# rzlblink_v2a.net
KiCad netlist of a schematic drawn in EAGLE
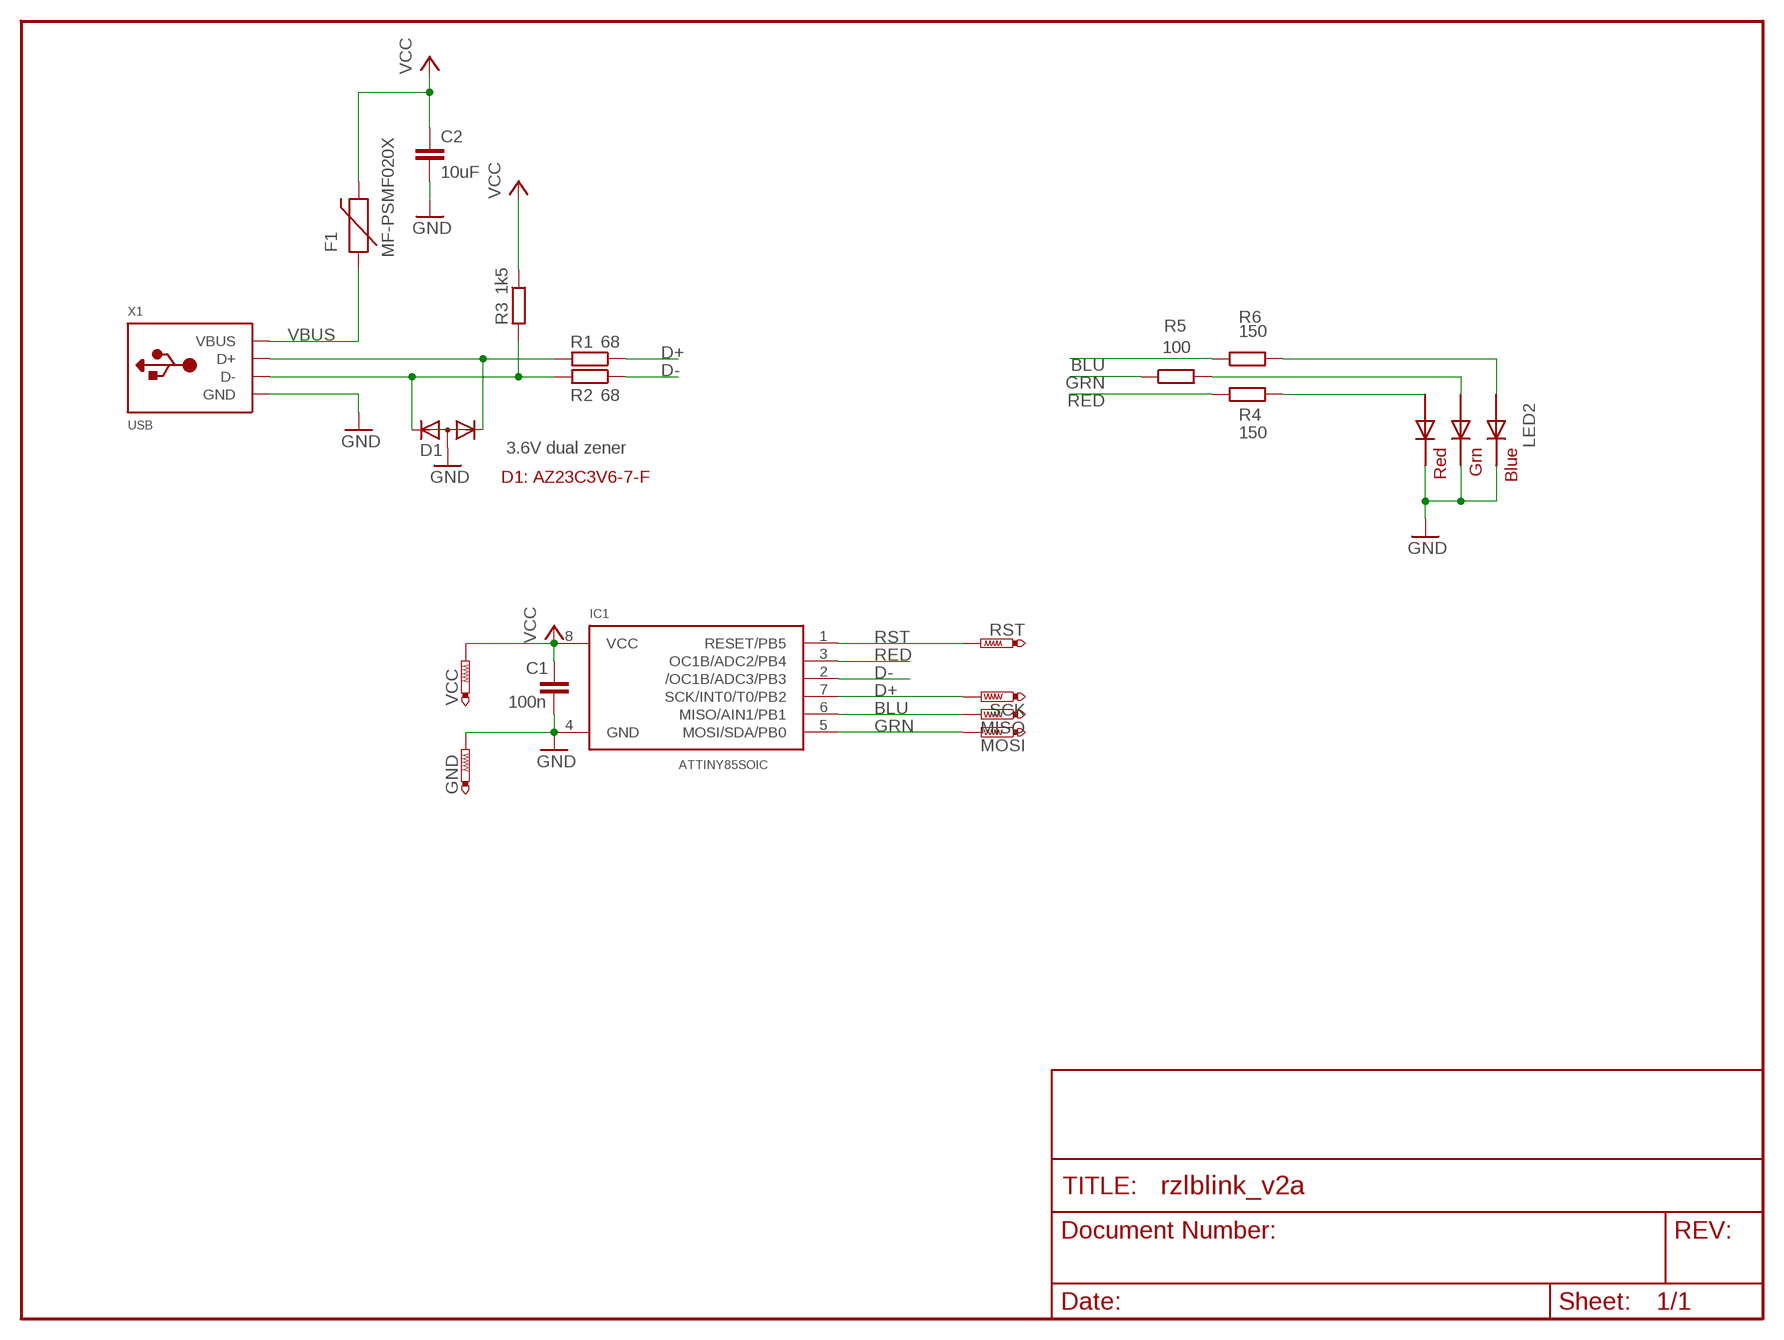
[diagram p0: schematic, sheet 1]

(export (version "E")
  (design (tool "Eeschema 10.0.6"))
  (components
    (comp (ref "C1")
      (value "100n")
      (footprint "eagle-import:C0805")
      (libsource (lib "eagle-import") (part "C-EUC0805"))
    )
    (comp (ref "C2")
      (value "10uF")
      (footprint "eagle-import:C0805")
      (libsource (lib "eagle-import") (part "C-EUC0805"))
    )
    (comp (ref "D1")
      (value "3.6V dual zener")
      (footprint "eagle-import:SOT23")
      (libsource (lib "eagle-import") (part "DIODE-2CA|ACSOT23"))
    )
    (comp (ref "F1")
      (value "MF-PSMF020X")
      (footprint "eagle-import:0805")
      (libsource (lib "eagle-import") (part "PTC0805"))
    )
    (comp (ref "GND")
      (value "PTR1TP10R")
      (footprint "eagle-import:TP10R")
      (libsource (lib "eagle-import") (part "PTR1TP10R"))
    )
    (comp (ref "IC1")
      (value "ATTINY85SOIC")
      (footprint "eagle-import:SO08-EIAJ")
      (libsource (lib "eagle-import") (part "ATTINY45SOIC"))
    )
    (comp (ref "LED2")
      (value "RGBLED5050")
      (footprint "eagle-import:RGBLED5050")
      (libsource (lib "eagle-import") (part "RGBLED5050"))
    )
    (comp (ref "MISO")
      (value "PTR1TP10R")
      (footprint "eagle-import:TP10R")
      (libsource (lib "eagle-import") (part "PTR1TP10R"))
    )
    (comp (ref "MOSI")
      (value "PTR1TP10R")
      (footprint "eagle-import:TP10R")
      (libsource (lib "eagle-import") (part "PTR1TP10R"))
    )
    (comp (ref "R1")
      (value "68")
      (footprint "eagle-import:R1206")
      (libsource (lib "eagle-import") (part "R-EU_R1206"))
    )
    (comp (ref "R2")
      (value "68")
      (footprint "eagle-import:R1206")
      (libsource (lib "eagle-import") (part "R-EU_R1206"))
    )
    (comp (ref "R3")
      (value "1k5")
      (footprint "eagle-import:R0805")
      (libsource (lib "eagle-import") (part "R-EU_R0805"))
    )
    (comp (ref "R4")
      (value "150")
      (footprint "eagle-import:R0805")
      (libsource (lib "eagle-import") (part "R-EU_R0805"))
    )
    (comp (ref "R5")
      (value "100")
      (footprint "eagle-import:R0805")
      (libsource (lib "eagle-import") (part "R-EU_R0805"))
    )
    (comp (ref "R6")
      (value "150")
      (footprint "eagle-import:R0805")
      (libsource (lib "eagle-import") (part "R-EU_R0805"))
    )
    (comp (ref "RST")
      (value "PTR1TP10R")
      (footprint "eagle-import:TP10R")
      (libsource (lib "eagle-import") (part "PTR1TP10R"))
    )
    (comp (ref "SCK")
      (value "PTR1TP10R")
      (footprint "eagle-import:TP10R")
      (libsource (lib "eagle-import") (part "PTR1TP10R"))
    )
    (comp (ref "VCC")
      (value "PTR1TP10R")
      (footprint "eagle-import:TP10R")
      (libsource (lib "eagle-import") (part "PTR1TP10R"))
    )
    (comp (ref "X1")
      (value "USB")
      (footprint "eagle-import:MOLEX-48037-1000")
      (libsource (lib "eagle-import") (part "USB"))
    )
  )
  (nets
    (net (code "1") (name "/BLU") (class "Default")
      (node (ref "IC1") (pin "6") (pinfunction "MISO/AIN1/PB1_6") (pintype "bidirectional"))
      (node (ref "MISO") (pin "TP") (pinfunction "TP_TP") (pintype "input"))
      (node (ref "R6") (pin "1") (pinfunction "1_1") (pintype "passive"))
    )
    (net (code "2") (name "/D+") (class "Default")
      (node (ref "IC1") (pin "7") (pinfunction "SCK/INT0/T0/PB2_7") (pintype "bidirectional"))
      (node (ref "R1") (pin "1") (pinfunction "1_1") (pintype "passive"))
      (node (ref "SCK") (pin "TP") (pinfunction "TP_TP") (pintype "input"))
    )
    (net (code "3") (name "/D-") (class "Default")
      (node (ref "IC1") (pin "2") (pinfunction "/OC1B/ADC3/PB3_2") (pintype "bidirectional"))
      (node (ref "R2") (pin "1") (pinfunction "1_1") (pintype "passive"))
    )
    (net (code "4") (name "/GRN") (class "Default")
      (node (ref "IC1") (pin "5") (pinfunction "MOSI/SDA/PB0_5") (pintype "bidirectional"))
      (node (ref "MOSI") (pin "TP") (pinfunction "TP_TP") (pintype "input"))
      (node (ref "R5") (pin "1") (pinfunction "1_1") (pintype "passive"))
    )
    (net (code "5") (name "/RED") (class "Default")
      (node (ref "IC1") (pin "3") (pinfunction "OC1B/ADC2/PB4_3") (pintype "bidirectional"))
      (node (ref "R4") (pin "1") (pinfunction "1_1") (pintype "passive"))
    )
    (net (code "6") (name "/RST") (class "Default")
      (node (ref "IC1") (pin "1") (pinfunction "RESET/PB5_1") (pintype "bidirectional"))
      (node (ref "RST") (pin "TP") (pinfunction "TP_TP") (pintype "input"))
    )
    (net (code "7") (name "/VBUS") (class "Default")
      (node (ref "F1") (pin "1") (pinfunction "1_1") (pintype "bidirectional"))
      (node (ref "X1") (pin "1") (pinfunction "VBUS_1") (pintype "power_in"))
    )
    (net (code "8") (name "GND") (class "Default")
      (node (ref "C1") (pin "2") (pinfunction "2_2") (pintype "passive"))
      (node (ref "C2") (pin "2") (pinfunction "2_2") (pintype "passive"))
      (node (ref "D1") (pin "3") (pinfunction "A_3") (pintype "passive"))
      (node (ref "GND") (pin "TP") (pinfunction "TP_TP") (pintype "input"))
      (node (ref "IC1") (pin "4") (pinfunction "GND_4") (pintype "bidirectional"))
      (node (ref "LED2") (pin "4") (pinfunction "BLUE_C_4") (pintype "bidirectional"))
      (node (ref "LED2") (pin "5") (pinfunction "RED_C_5") (pintype "bidirectional"))
      (node (ref "LED2") (pin "6") (pinfunction "GREEN_C_6") (pintype "bidirectional"))
      (node (ref "X1") (pin "4") (pinfunction "GND_4") (pintype "power_in"))
    )
    (net (code "9") (name "Net-(D1-K1)") (class "Default")
      (node (ref "D1") (pin "1") (pinfunction "K1_1") (pintype "passive"))
      (node (ref "R1") (pin "2") (pinfunction "2_2") (pintype "passive"))
      (node (ref "X1") (pin "3") (pinfunction "D+_3") (pintype "bidirectional"))
    )
    (net (code "10") (name "Net-(D1-K2)") (class "Default")
      (node (ref "D1") (pin "2") (pinfunction "K2_2") (pintype "passive"))
      (node (ref "R2") (pin "2") (pinfunction "2_2") (pintype "passive"))
      (node (ref "R3") (pin "2") (pinfunction "2_2") (pintype "passive"))
      (node (ref "X1") (pin "2") (pinfunction "D-_2") (pintype "bidirectional"))
    )
    (net (code "11") (name "Net-(LED2-BLUE_A)") (class "Default")
      (node (ref "LED2") (pin "3") (pinfunction "BLUE_A_3") (pintype "bidirectional"))
      (node (ref "R6") (pin "2") (pinfunction "2_2") (pintype "passive"))
    )
    (net (code "12") (name "Net-(LED2-GREEN_A)") (class "Default")
      (node (ref "LED2") (pin "1") (pinfunction "GREEN_A_1") (pintype "bidirectional"))
      (node (ref "R5") (pin "2") (pinfunction "2_2") (pintype "passive"))
    )
    (net (code "13") (name "Net-(LED2-RED_A)") (class "Default")
      (node (ref "LED2") (pin "2") (pinfunction "RED_A_2") (pintype "bidirectional"))
      (node (ref "R4") (pin "2") (pinfunction "2_2") (pintype "passive"))
    )
    (net (code "14") (name "VCC") (class "Default")
      (node (ref "C1") (pin "1") (pinfunction "1_1") (pintype "passive"))
      (node (ref "C2") (pin "1") (pinfunction "1_1") (pintype "passive"))
      (node (ref "F1") (pin "2") (pinfunction "2_2") (pintype "bidirectional"))
      (node (ref "IC1") (pin "8") (pinfunction "VCC_8") (pintype "bidirectional"))
      (node (ref "R3") (pin "1") (pinfunction "1_1") (pintype "passive"))
      (node (ref "VCC") (pin "TP") (pinfunction "TP_TP") (pintype "input"))
    )
  )
)
